# phantom_power.net
KiCad netlist of a schematic drawn in EAGLE
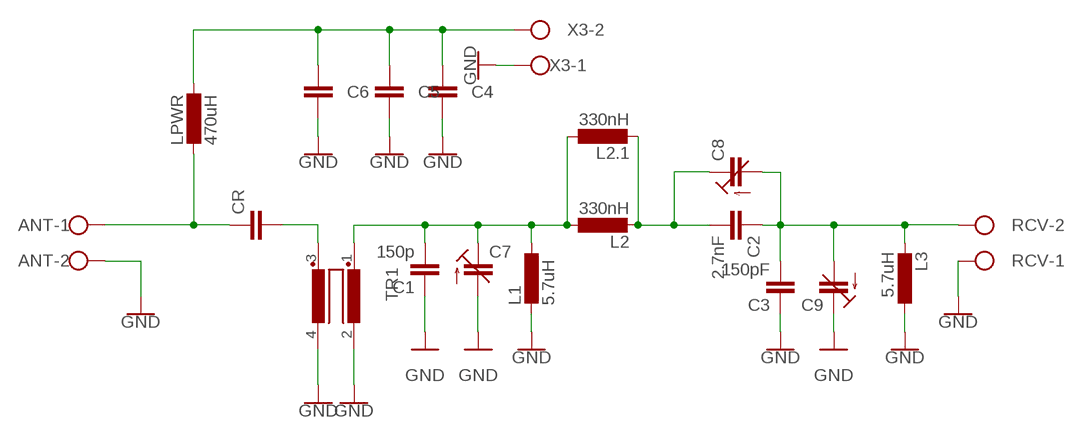
[diagram p0: schematic, sheet 1]

(export (version "E")
  (design (tool "Eeschema 10.0.6"))
  (components
    (comp (ref "ANT")
      (value "W237-102")
      (footprint "eagle-import:W237-102")
      (fields (field (name "MPN") "237-102"))
      (libsource (lib "eagle-import") (part "W237-102"))
    )
    (comp (ref "C1")
      (value "150p")
      (footprint "eagle-import:C1206K")
      (libsource (lib "eagle-import") (part "C-EUC1206K"))
    )
    (comp (ref "C2")
      (value "2.7nF")
      (footprint "eagle-import:C1206K")
      (libsource (lib "eagle-import") (part "C-EUC1206K"))
    )
    (comp (ref "C3")
      (value "150pF")
      (footprint "eagle-import:C1206K")
      (libsource (lib "eagle-import") (part "C-EUC1206K"))
    )
    (comp (ref "C4")
      (value "C-EUC1206K")
      (footprint "eagle-import:C1206K")
      (libsource (lib "eagle-import") (part "C-EUC1206K"))
    )
    (comp (ref "C5")
      (value "C-EUC1206K")
      (footprint "eagle-import:C1206K")
      (libsource (lib "eagle-import") (part "C-EUC1206K"))
    )
    (comp (ref "C6")
      (value "C-EUC1206K")
      (footprint "eagle-import:C1206K")
      (libsource (lib "eagle-import") (part "C-EUC1206K"))
    )
    (comp (ref "C7")
      (value "C-TRIMM3050.504")
      (footprint "eagle-import:CTRIM3050.504")
      (libsource (lib "eagle-import") (part "C-TRIMM3050.504"))
    )
    (comp (ref "C8")
      (value "C-TRIMM3050.504")
      (footprint "eagle-import:CTRIM3050.504")
      (libsource (lib "eagle-import") (part "C-TRIMM3050.504"))
    )
    (comp (ref "C9")
      (value "C-TRIMM3050.504")
      (footprint "eagle-import:CTRIM3050.504")
      (libsource (lib "eagle-import") (part "C-TRIMM3050.504"))
    )
    (comp (ref "CR")
      (value "C-EUC1206K")
      (footprint "eagle-import:C1206K")
      (libsource (lib "eagle-import") (part "C-EUC1206K"))
    )
    (comp (ref "L1")
      (value "5.7uH")
      (footprint "eagle-import:0204_7")
      (libsource (lib "eagle-import") (part "L-EU0204/7"))
    )
    (comp (ref "L2")
      (value "330nH")
      (footprint "eagle-import:L1812")
      (libsource (lib "eagle-import") (part "L-EUL1812"))
    )
    (comp (ref "L2.1")
      (value "330nH")
      (footprint "eagle-import:0204_7")
      (libsource (lib "eagle-import") (part "L-EU0204/7"))
    )
    (comp (ref "L3")
      (value "5.7uH")
      (footprint "eagle-import:0204_7")
      (libsource (lib "eagle-import") (part "L-EU0204/7"))
    )
    (comp (ref "LPWR")
      (value "470uH")
      (footprint "eagle-import:0204_7")
      (libsource (lib "eagle-import") (part "L-EU0204/7"))
    )
    (comp (ref "RCV")
      (value "W237-102")
      (footprint "eagle-import:W237-102")
      (fields (field (name "MPN") "237-102"))
      (libsource (lib "eagle-import") (part "W237-102"))
    )
    (comp (ref "TR1")
      (value "R1405UB1/2")
      (footprint "eagle-import:B1_2")
      (libsource (lib "eagle-import") (part "R1405UB1/2"))
    )
    (comp (ref "X3")
      (value "W237-102")
      (footprint "eagle-import:W237-102")
      (fields (field (name "MPN") "237-102"))
      (libsource (lib "eagle-import") (part "W237-102"))
    )
  )
  (nets
    (net (code "1") (name "GND") (class "Default")
      (node (ref "ANT") (pin "2") (pinfunction "KL_2") (pintype "passive"))
      (node (ref "C1") (pin "1") (pinfunction "1_1") (pintype "passive"))
      (node (ref "C3") (pin "1") (pinfunction "1_1") (pintype "passive"))
      (node (ref "C4") (pin "2") (pinfunction "2_2") (pintype "passive"))
      (node (ref "C5") (pin "2") (pinfunction "2_2") (pintype "passive"))
      (node (ref "C6") (pin "2") (pinfunction "2_2") (pintype "passive"))
      (node (ref "C7") (pin "2") (pinfunction "A_2") (pintype "passive"))
      (node (ref "C9") (pin "1") (pinfunction "E_1") (pintype "passive"))
      (node (ref "L1") (pin "2") (pinfunction "2_2") (pintype "passive"))
      (node (ref "L3") (pin "1") (pinfunction "1_1") (pintype "passive"))
      (node (ref "RCV") (pin "1") (pinfunction "KL_1") (pintype "passive"))
      (node (ref "TR1") (pin "2") (pinfunction "2_2") (pintype "passive"))
      (node (ref "TR1") (pin "4") (pinfunction "4_4") (pintype "passive"))
      (node (ref "X3") (pin "1") (pinfunction "KL_1") (pintype "passive"))
    )
    (net (code "2") (name "Net-(ANTA-KL)") (class "Default")
      (node (ref "ANT") (pin "1") (pinfunction "KL_1") (pintype "passive"))
      (node (ref "CR") (pin "1") (pinfunction "1_1") (pintype "passive"))
      (node (ref "LPWR") (pin "2") (pinfunction "2_2") (pintype "passive"))
    )
    (net (code "3") (name "Net-(C7-E)") (class "Default")
      (node (ref "C1") (pin "2") (pinfunction "2_2") (pintype "passive"))
      (node (ref "C7") (pin "1") (pinfunction "E_1") (pintype "passive"))
      (node (ref "L1") (pin "1") (pinfunction "1_1") (pintype "passive"))
      (node (ref "L2") (pin "1") (pinfunction "1_1") (pintype "passive"))
      (node (ref "L2.1") (pin "1") (pinfunction "1_1") (pintype "passive"))
      (node (ref "TR1") (pin "1") (pinfunction "1_1") (pintype "passive"))
    )
    (net (code "4") (name "Net-(C8-A)") (class "Default")
      (node (ref "C2") (pin "1") (pinfunction "1_1") (pintype "passive"))
      (node (ref "C3") (pin "2") (pinfunction "2_2") (pintype "passive"))
      (node (ref "C8") (pin "2") (pinfunction "A_2") (pintype "passive"))
      (node (ref "C9") (pin "2") (pinfunction "A_2") (pintype "passive"))
      (node (ref "L3") (pin "2") (pinfunction "2_2") (pintype "passive"))
      (node (ref "RCV") (pin "2") (pinfunction "KL_2") (pintype "passive"))
    )
    (net (code "5") (name "Net-(C8-E)") (class "Default")
      (node (ref "C2") (pin "2") (pinfunction "2_2") (pintype "passive"))
      (node (ref "C8") (pin "1") (pinfunction "E_1") (pintype "passive"))
      (node (ref "L2") (pin "2") (pinfunction "2_2") (pintype "passive"))
      (node (ref "L2.1") (pin "2") (pinfunction "2_2") (pintype "passive"))
    )
    (net (code "6") (name "Net-(CR-Pad2)") (class "Default")
      (node (ref "CR") (pin "2") (pinfunction "2_2") (pintype "passive"))
      (node (ref "TR1") (pin "3") (pinfunction "3_3") (pintype "passive"))
    )
    (net (code "7") (name "Net-(X3B-KL)") (class "Default")
      (node (ref "C4") (pin "1") (pinfunction "1_1") (pintype "passive"))
      (node (ref "C5") (pin "1") (pinfunction "1_1") (pintype "passive"))
      (node (ref "C6") (pin "1") (pinfunction "1_1") (pintype "passive"))
      (node (ref "LPWR") (pin "1") (pinfunction "1_1") (pintype "passive"))
      (node (ref "X3") (pin "2") (pinfunction "KL_2") (pintype "passive"))
    )
  )
)
